# XRACER-SD-USB-R07.net
KiCad netlist of a schematic drawn in Altium Designer
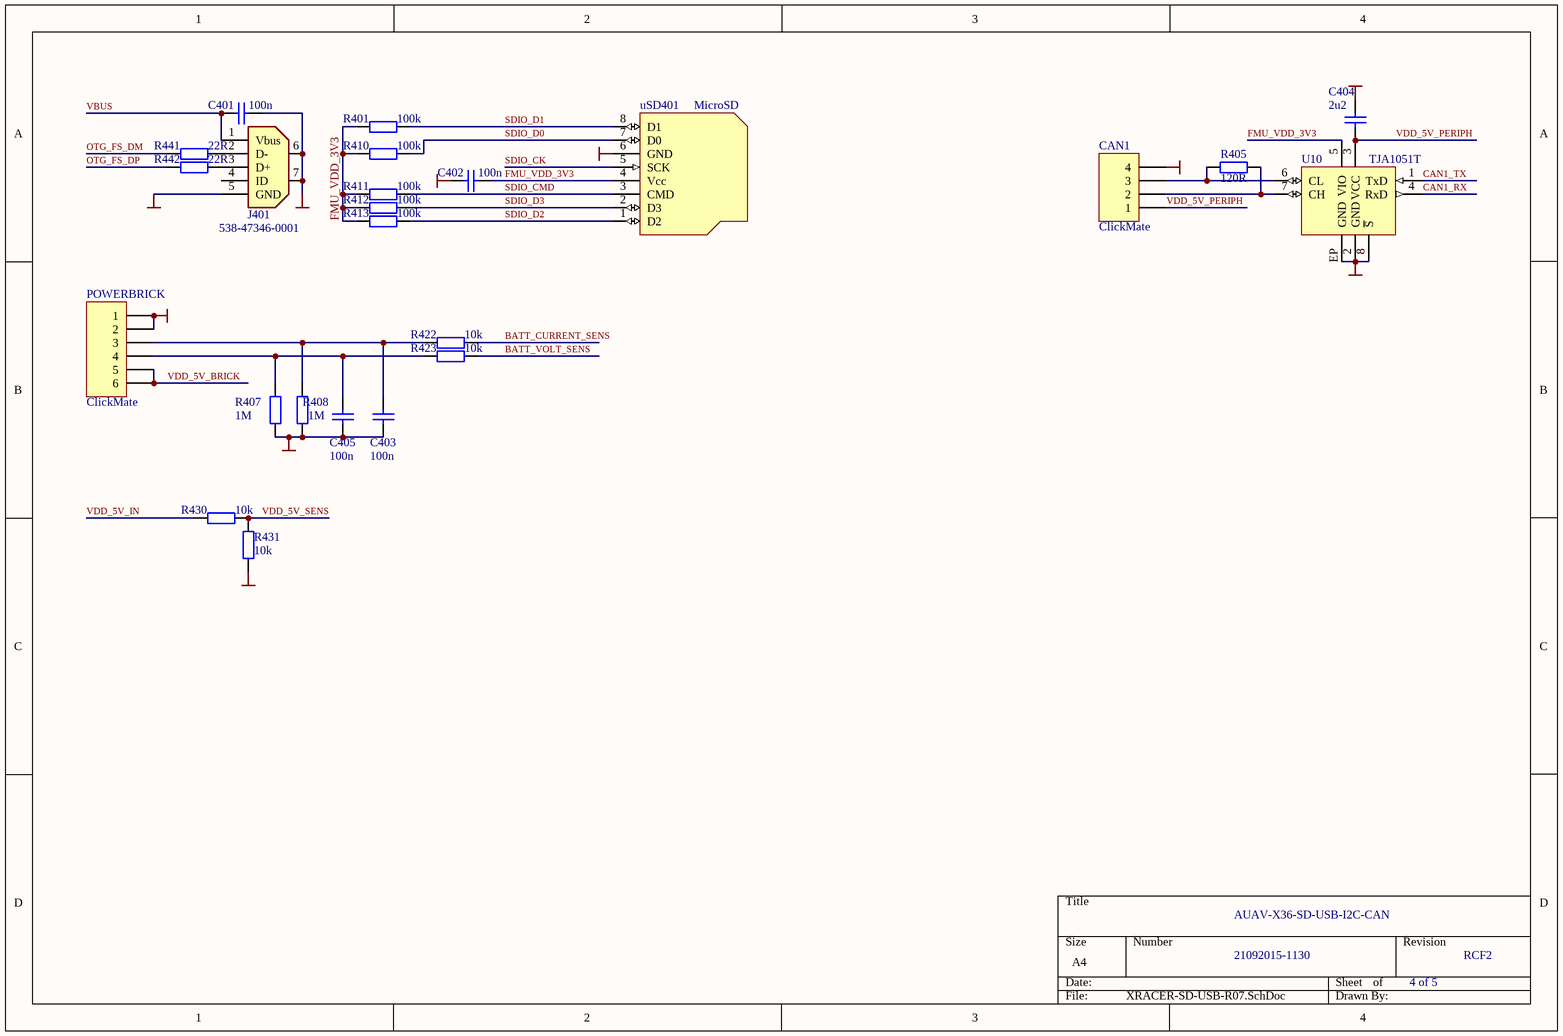
[diagram p0: XRACER-SD-USB-R07.SchDoc]

(export (version "E")
  (design (tool "Eeschema 10.0.6"))
  (components
    (comp (ref "C401")
      (value "100n")
      (footprint "0402A")
      (description "Capacitor")
      (fields (field (name "PUBLISHER") "Altium Limited"))
      (libsource (lib "Miscellaneous Devices") (part "Cap"))
    )
    (comp (ref "C402")
      (value "100n")
      (footprint "0402A")
      (description "Capacitor")
      (fields (field (name "PUBLISHER") "Altium Limited"))
      (libsource (lib "Miscellaneous Devices") (part "Cap"))
    )
    (comp (ref "C403")
      (value "100n")
      (footprint "0402A")
      (description "Capacitor")
      (fields (field (name "PUBLISHER") "Altium Limited"))
      (libsource (lib "Miscellaneous Devices") (part "Cap"))
    )
    (comp (ref "C404")
      (value "2u2")
      (footprint "0603A")
      (description "Capacitor")
      (fields (field (name "PUBLISHER") "Altium Limited"))
      (libsource (lib "Miscellaneous Devices") (part "Cap"))
    )
    (comp (ref "C405")
      (value "100n")
      (footprint "0402A")
      (description "Capacitor")
      (fields (field (name "PUBLISHER") "Altium Limited"))
      (libsource (lib "Miscellaneous Devices") (part "Cap"))
    )
    (comp (ref "CAN1")
      (value "ClickMate")
      (footprint "Molex_1.25_click_4")
      (description "Header, 4-Pin")
      (fields (field (name "PUBLISHER") "Altium Limited"))
      (libsource (lib "Miscellaneous Connectors") (part "Header 4"))
    )
    (comp (ref "J401")
      (value "miniUSB")
      (footprint "USBmicro_B")
      (fields (field (name "MOUSER PART NUMBER") "538-47346-0001"))
      (libsource (lib "My_Altium") (part "MicroUSB"))
    )
    (comp (ref "POWERBRICK")
      (value "ClickMate")
      (footprint "Molex_Clok_1.25_6H")
      (description "Header, 6-Pin")
      (fields (field (name "PUBLISHER") "Altium Limited"))
      (libsource (lib "Miscellaneous Connectors") (part "Header 6"))
    )
    (comp (ref "R401")
      (value "100k")
      (footprint "0402A")
      (description "Resistor")
      (fields (field (name "PUBLISHER") "Altium Limited"))
      (libsource (lib "Miscellaneous Devices") (part "Res2"))
    )
    (comp (ref "R405")
      (value "120R")
      (footprint "0603A")
      (description "Resistor")
      (fields (field (name "PUBLISHER") "Altium Limited"))
      (libsource (lib "Miscellaneous Devices") (part "Res2"))
    )
    (comp (ref "R407")
      (value "1M")
      (footprint "0402A")
      (description "Resistor")
      (fields (field (name "PUBLISHER") "Altium Limited"))
      (libsource (lib "") (part "Res2_1"))
    )
    (comp (ref "R408")
      (value "1M")
      (footprint "0402A")
      (description "Resistor")
      (fields (field (name "PUBLISHER") "Altium Limited"))
      (libsource (lib "") (part "Res2_1"))
    )
    (comp (ref "R410")
      (value "100k")
      (footprint "0402A")
      (description "Resistor")
      (fields (field (name "PUBLISHER") "Altium Limited"))
      (libsource (lib "Miscellaneous Devices") (part "Res2"))
    )
    (comp (ref "R411")
      (value "100k")
      (footprint "0402A")
      (description "Resistor")
      (fields (field (name "PUBLISHER") "Altium Limited"))
      (libsource (lib "Miscellaneous Devices") (part "Res2"))
    )
    (comp (ref "R412")
      (value "100k")
      (footprint "0402A")
      (description "Resistor")
      (fields (field (name "PUBLISHER") "Altium Limited"))
      (libsource (lib "Miscellaneous Devices") (part "Res2"))
    )
    (comp (ref "R413")
      (value "100k")
      (footprint "0402A")
      (description "Resistor")
      (fields (field (name "PUBLISHER") "Altium Limited"))
      (libsource (lib "Miscellaneous Devices") (part "Res2"))
    )
    (comp (ref "R422")
      (value "10k")
      (footprint "0402A")
      (description "Resistor")
      (fields (field (name "PUBLISHER") "Altium Limited"))
      (libsource (lib "Miscellaneous Devices") (part "Res2"))
    )
    (comp (ref "R423")
      (value "10k")
      (footprint "0402A")
      (description "Resistor")
      (fields (field (name "PUBLISHER") "Altium Limited"))
      (libsource (lib "Miscellaneous Devices") (part "Res2"))
    )
    (comp (ref "R430")
      (value "10k")
      (footprint "0402A")
      (description "Resistor")
      (fields (field (name "PUBLISHER") "Altium Limited"))
      (libsource (lib "Miscellaneous Devices") (part "Res2"))
    )
    (comp (ref "R431")
      (value "10k")
      (footprint "0402A")
      (description "Resistor")
      (fields (field (name "PUBLISHER") "Altium Limited"))
      (libsource (lib "") (part "Res2_1"))
    )
    (comp (ref "R441")
      (value "22R")
      (footprint "0402A")
      (description "Resistor")
      (fields (field (name "PUBLISHER") "Altium Limited"))
      (libsource (lib "Miscellaneous Devices") (part "Res2"))
    )
    (comp (ref "R442")
      (value "22R")
      (footprint "0402A")
      (description "Resistor")
      (fields (field (name "PUBLISHER") "Altium Limited"))
      (libsource (lib "Miscellaneous Devices") (part "Res2"))
    )
    (comp (ref "U10")
      (value "TJA1051T")
      (footprint "8DFN_3x3")
      (libsource (lib "My_Altium") (part "TJA1051T"))
    )
    (comp (ref "uSD401")
      (value "MicroSD")
      (footprint "MicroSD_China_01")
      (libsource (lib "My_Altium") (part "MicroSD"))
    )
  )
  (nets
    (net (code "1") (name "/BATT_CURRENT_SENS") (class "Default")
      (node (ref "R422") (pin "1") (pinfunction "1_1") (pintype "passive"))
    )
    (net (code "2") (name "/BATT_VOLT_SENS") (class "Default")
      (node (ref "R423") (pin "1") (pinfunction "1_1") (pintype "passive"))
    )
    (net (code "3") (name "/CAN1_RX") (class "Default")
      (node (ref "U10") (pin "4") (pinfunction "RxD_4") (pintype "output"))
    )
    (net (code "4") (name "/CAN1_TX") (class "Default")
      (node (ref "U10") (pin "1") (pinfunction "TxD_1") (pintype "input"))
    )
    (net (code "5") (name "/FMU_VDD_3V3") (class "Default")
      (node (ref "C402") (pin "1") (pinfunction "1_1") (pintype "passive"))
      (node (ref "R401") (pin "2") (pinfunction "2_2") (pintype "passive"))
      (node (ref "R410") (pin "2") (pinfunction "2_2") (pintype "passive"))
      (node (ref "R411") (pin "2") (pinfunction "2_2") (pintype "passive"))
      (node (ref "R412") (pin "2") (pinfunction "2_2") (pintype "passive"))
      (node (ref "R413") (pin "2") (pinfunction "2_2") (pintype "passive"))
      (node (ref "U10") (pin "5") (pinfunction "VIO_5") (pintype "power_in"))
      (node (ref "uSD401") (pin "4") (pinfunction "Vcc_4") (pintype "power_in"))
    )
    (net (code "6") (name "/OTG_FS_DM") (class "Default")
      (node (ref "R441") (pin "2") (pinfunction "2_2") (pintype "passive"))
    )
    (net (code "7") (name "/OTG_FS_DP") (class "Default")
      (node (ref "R442") (pin "2") (pinfunction "2_2") (pintype "passive"))
    )
    (net (code "8") (name "/SDIO_CK") (class "Default")
      (node (ref "uSD401") (pin "5") (pinfunction "SCK_5") (pintype "input"))
    )
    (net (code "9") (name "/SDIO_CMD") (class "Default")
      (node (ref "R411") (pin "1") (pinfunction "1_1") (pintype "passive"))
      (node (ref "uSD401") (pin "3") (pinfunction "CMD_3") (pintype "passive"))
    )
    (net (code "10") (name "/SDIO_D0") (class "Default")
      (node (ref "R410") (pin "1") (pinfunction "1_1") (pintype "passive"))
      (node (ref "uSD401") (pin "7") (pinfunction "D0_7") (pintype "bidirectional"))
    )
    (net (code "11") (name "/SDIO_D1") (class "Default")
      (node (ref "R401") (pin "1") (pinfunction "1_1") (pintype "passive"))
      (node (ref "uSD401") (pin "8") (pinfunction "D1_8") (pintype "bidirectional"))
    )
    (net (code "12") (name "/SDIO_D2") (class "Default")
      (node (ref "R413") (pin "1") (pinfunction "1_1") (pintype "passive"))
      (node (ref "uSD401") (pin "1") (pinfunction "D2_1") (pintype "bidirectional"))
    )
    (net (code "13") (name "/SDIO_D3") (class "Default")
      (node (ref "R412") (pin "1") (pinfunction "1_1") (pintype "passive"))
      (node (ref "uSD401") (pin "2") (pinfunction "D3_2") (pintype "bidirectional"))
    )
    (net (code "14") (name "/VBUS") (class "Default")
      (node (ref "C401") (pin "2") (pinfunction "2_2") (pintype "passive"))
      (node (ref "J401") (pin "1") (pinfunction "Vbus_1") (pintype "power_in"))
    )
    (net (code "15") (name "/VDD_5V_BRICK") (class "Default")
      (node (ref "POWERBRICK") (pin "5") (pinfunction "5_5") (pintype "passive"))
      (node (ref "POWERBRICK") (pin "6") (pinfunction "6_6") (pintype "passive"))
    )
    (net (code "16") (name "/VDD_5V_IN") (class "Default")
      (node (ref "R430") (pin "2") (pinfunction "2_2") (pintype "passive"))
    )
    (net (code "17") (name "/VDD_5V_PERIPH") (class "Default")
      (node (ref "C404") (pin "2") (pinfunction "2_2") (pintype "passive"))
      (node (ref "CAN1") (pin "1") (pinfunction "1_1") (pintype "passive"))
      (node (ref "U10") (pin "3") (pinfunction "VCC_3") (pintype "power_in"))
    )
    (net (code "18") (name "/VDD_5V_SENS") (class "Default")
      (node (ref "R430") (pin "1") (pinfunction "1_1") (pintype "passive"))
      (node (ref "R431") (pin "1") (pinfunction "1_1") (pintype "passive"))
    )
    (net (code "19") (name "GND") (class "Default")
      (node (ref "C401") (pin "1") (pinfunction "1_1") (pintype "passive"))
      (node (ref "C402") (pin "2") (pinfunction "2_2") (pintype "passive"))
      (node (ref "C403") (pin "2") (pinfunction "2_2") (pintype "passive"))
      (node (ref "C404") (pin "1") (pinfunction "1_1") (pintype "passive"))
      (node (ref "C405") (pin "2") (pinfunction "2_2") (pintype "passive"))
      (node (ref "CAN1") (pin "4") (pinfunction "4_4") (pintype "passive"))
      (node (ref "J401") (pin "5") (pinfunction "GND_5") (pintype "power_in"))
      (node (ref "J401") (pin "6") (pinfunction "GND_6") (pintype "passive"))
      (node (ref "J401") (pin "7") (pinfunction "GND_7") (pintype "passive"))
      (node (ref "POWERBRICK") (pin "1") (pinfunction "1_1") (pintype "passive"))
      (node (ref "POWERBRICK") (pin "2") (pinfunction "2_2") (pintype "passive"))
      (node (ref "R407") (pin "2") (pinfunction "2_2") (pintype "passive"))
      (node (ref "R408") (pin "2") (pinfunction "2_2") (pintype "passive"))
      (node (ref "R431") (pin "2") (pinfunction "2_2") (pintype "passive"))
      (node (ref "U10") (pin "2") (pinfunction "GND_2") (pintype "power_in"))
      (node (ref "U10") (pin "8") (pinfunction "~{S}_8") (pintype "passive"))
      (node (ref "U10") (pin "EP") (pinfunction "GND_EP") (pintype "power_in"))
      (node (ref "uSD401") (pin "6") (pinfunction "GND_6") (pintype "power_in"))
    )
    (net (code "20") (name "Net-(C403-Pad1)") (class "Default")
      (node (ref "C403") (pin "1") (pinfunction "1_1") (pintype "passive"))
      (node (ref "POWERBRICK") (pin "3") (pinfunction "3_3") (pintype "passive"))
      (node (ref "R408") (pin "1") (pinfunction "1_1") (pintype "passive"))
      (node (ref "R422") (pin "2") (pinfunction "2_2") (pintype "passive"))
    )
    (net (code "21") (name "Net-(C405-Pad1)") (class "Default")
      (node (ref "C405") (pin "1") (pinfunction "1_1") (pintype "passive"))
      (node (ref "POWERBRICK") (pin "4") (pinfunction "4_4") (pintype "passive"))
      (node (ref "R407") (pin "1") (pinfunction "1_1") (pintype "passive"))
      (node (ref "R423") (pin "2") (pinfunction "2_2") (pintype "passive"))
    )
    (net (code "22") (name "Net-(J401-D+)") (class "Default")
      (node (ref "J401") (pin "3") (pinfunction "D+_3") (pintype "passive"))
      (node (ref "R442") (pin "1") (pinfunction "1_1") (pintype "passive"))
    )
    (net (code "23") (name "Net-(J401-D-)") (class "Default")
      (node (ref "J401") (pin "2") (pinfunction "D-_2") (pintype "passive"))
      (node (ref "R441") (pin "1") (pinfunction "1_1") (pintype "passive"))
    )
    (net (code "24") (name "Net-(U10-CH)") (class "Default")
      (node (ref "CAN1") (pin "2") (pinfunction "2_2") (pintype "passive"))
      (node (ref "R405") (pin "1") (pinfunction "1_1") (pintype "passive"))
      (node (ref "U10") (pin "7") (pinfunction "CH_7") (pintype "bidirectional"))
    )
    (net (code "25") (name "Net-(U10-CL)") (class "Default")
      (node (ref "CAN1") (pin "3") (pinfunction "3_3") (pintype "passive"))
      (node (ref "R405") (pin "2") (pinfunction "2_2") (pintype "passive"))
      (node (ref "U10") (pin "6") (pinfunction "CL_6") (pintype "bidirectional"))
    )
    (net (code "26") (name "unconnected-(J401-ID-Pad4)") (class "Default")
      (node (ref "J401") (pin "4") (pinfunction "ID_4") (pintype "passive"))
    )
  )
)
